# 24V_to_5V_Buck_Converter.net
KiCad netlist of a schematic drawn in Altium Designer
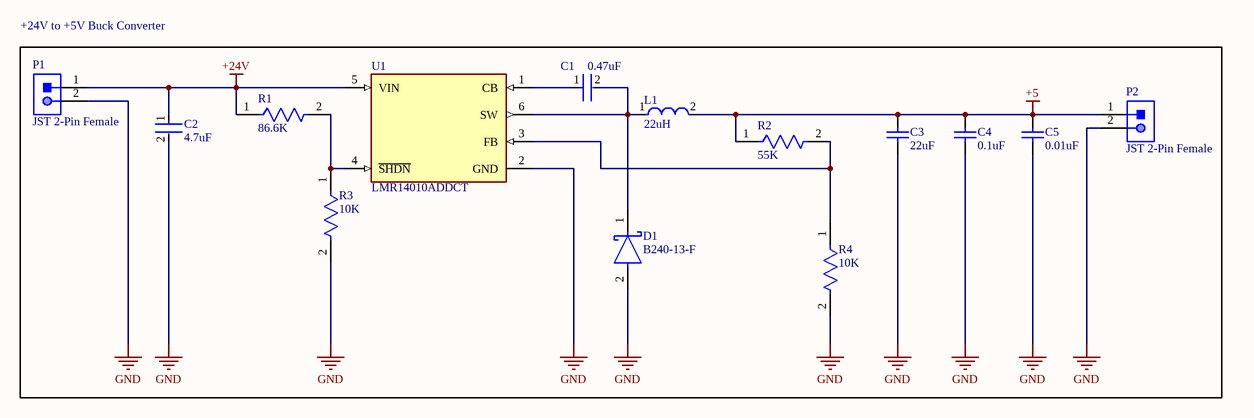
[diagram p0: 24V_to_5V_Buck_Converter.SchDoc]

(export (version "E")
  (design (tool "Eeschema 10.0.6"))
  (components
    (comp (ref "C1")
      (value "0.47uF")
      (footprint "FP-CC0603-DA-MFG")
      (description "CAP CER 0.47UF 16V X7R 0603")
      (fields
        (field (name "MANUFACTURER PART NUMBER") "CC0603KRX7R7BB474")
        (field (name "MANUFACTURER") "YAGEO")
      )
      (libsource (lib "Altium Content Vault") (part "11868f565c42a9108669ba33697ecf6"))
    )
    (comp (ref "C2")
      (value "4.7uF")
      (footprint "FP-CC1206-1_25-MFG")
      (description "CAP CER 4.7UF 50V X7R 1206")
      (fields (field (name "MANUFACTURER PART NUMBER") "CC1206KKX7R9BB475") (field (name "TOLERANCE") "0.1"))
      (libsource (lib "Altium Content Vault") (part "11868f565c42a9108669ba33697ecf6"))
    )
    (comp (ref "C3")
      (value "22uF")
      (footprint "CAPC1206(3216)190_L")
      (description "CAP 22uF 16V -20% to +80% 1206 (3216 Metric) Thickness 1.9mm SMD")
      (fields (field (name "TOLERANCE") "-20% to +80%"))
      (libsource (lib "Altium Content Vault") (part "CAP"))
    )
    (comp (ref "C4")
      (value "0.1uF")
      (footprint "CAPC1206(3216)190_L")
      (description "CAP 22uF 16V -20% to +80% 1206 (3216 Metric) Thickness 1.9mm SMD")
      (fields (field (name "TOLERANCE") "-20% to +80%"))
      (libsource (lib "Altium Content Vault") (part "CAP"))
    )
    (comp (ref "C5")
      (value "0.01uF")
      (footprint "CAPC1206(3216)190_L")
      (description "CAP 22uF 16V -20% to +80% 1206 (3216 Metric) Thickness 1.9mm SMD")
      (fields (field (name "TOLERANCE") "-20% to +80%"))
      (libsource (lib "Altium Content Vault") (part "CAP"))
    )
    (comp (ref "D1")
      (value "B240-13-F")
      (footprint "FP-SMB-MFG")
      (description "DIODE SCHOTTKY 40V 2A SMB")
      (fields
        (field (name "MANUFACTURER") "Diodes Inc.")
        (field (name "OCTOPART") "https://octopart.com/b240-13-f-diodes+inc.-325780")
      )
      (libsource (lib "Altium Content Vault") (part "1d6ec82d83fb6aee721767c19dac4b9"))
    )
    (comp (ref "L1")
      (value "22uH")
      (footprint "FP-IHLP-2525CZ-FP_2_413x3-MFG")
      (description "Commercial Inductors, Low DCR Series 22uH 2.9A 135mΩ 20%")
      (fields (field (name "TOLERANCE") "20%"))
      (libsource (lib "Altium Content Vault") (part "725321dda6339637d4d059423bc1c3c"))
    )
    (comp (ref "P1")
      (value "JST 2-Pin Female")
      (footprint "JST-S2B-PH-K-S_V")
      (fields (field (name "TOLERANCE") "20%"))
      (libsource (lib "") (part "CN-1P-M-R2_1"))
    )
    (comp (ref "P2")
      (value "JST 2-Pin Female")
      (footprint "JST-S2B-PH-K-S_V")
      (fields (field (name "TOLERANCE") "20%"))
      (libsource (lib "Altium Content Vault") (part "CN-1P-M-R2"))
    )
    (comp (ref "R1")
      (value "86.6K")
      (footprint "FP-RC0603-MFG")
      (description "RES SMD 0 OHM JUMPER 1/10W 0603")
      (fields
        (field (name "TOLERANCE") "1%")
        (field (name "OCTOPART") "https://octopart.com/rc0603fr-070rl-yageo-1180803")
      )
      (libsource (lib "Altium Content Vault") (part "1029c3af85768c4190bb7ad29bc67b5"))
    )
    (comp (ref "R2")
      (value "55K")
      (footprint "FP-RC0603-MFG")
      (description "RES SMD 0 OHM JUMPER 1/10W 0603")
      (fields
        (field (name "TOLERANCE") "1%")
        (field (name "OCTOPART") "https://octopart.com/rc0603fr-070rl-yageo-1180803")
      )
      (libsource (lib "Altium Content Vault") (part "1029c3af85768c4190bb7ad29bc67b5"))
    )
    (comp (ref "R3")
      (value "10K")
      (footprint "FP-RC0603-MFG")
      (description "RES SMD 0 OHM JUMPER 1/10W 0603")
      (fields
        (field (name "TOLERANCE") "1%")
        (field (name "OCTOPART") "https://octopart.com/rc0603fr-070rl-yageo-1180803")
      )
      (libsource (lib "Altium Content Vault") (part "1029c3af85768c4190bb7ad29bc67b5"))
    )
    (comp (ref "R4")
      (value "10K")
      (footprint "FP-RC0603-MFG")
      (description "RES SMD 0 OHM JUMPER 1/10W 0603")
      (fields
        (field (name "TOLERANCE") "1%")
        (field (name "OCTOPART") "https://octopart.com/rc0603fr-070rl-yageo-1180803")
      )
      (libsource (lib "Altium Content Vault") (part "1029c3af85768c4190bb7ad29bc67b5"))
    )
    (comp (ref "U1")
      (value "LMR14010ADDCT")
      (footprint "FP-DDC0006A-IPC_C")
      (description "IC REG BUCK ADJ 1A TSOT23-6")
      (libsource (lib "Altium Content Vault") (part "121dc64c8900d5d4b1f77199f935d68"))
    )
  )
  (nets
    (net (code "1") (name "+5") (class "Default")
      (node (ref "C3") (pin "2") (pinfunction "2_2") (pintype "passive"))
      (node (ref "C4") (pin "2") (pinfunction "2_2") (pintype "passive"))
      (node (ref "C5") (pin "2") (pinfunction "2_2") (pintype "passive"))
      (node (ref "L1") (pin "2") (pinfunction "2_2") (pintype "passive"))
      (node (ref "P2") (pin "1") (pinfunction "1_1") (pintype "passive"))
      (node (ref "R2") (pin "1") (pinfunction "1_1") (pintype "passive"))
    )
    (net (code "2") (name "+24V") (class "Default")
      (node (ref "C2") (pin "1") (pinfunction "1_1") (pintype "passive"))
      (node (ref "P1") (pin "1") (pinfunction "1_1") (pintype "passive"))
      (node (ref "R1") (pin "1") (pinfunction "1_1") (pintype "passive"))
      (node (ref "U1") (pin "5") (pinfunction "VIN_5") (pintype "input"))
    )
    (net (code "3") (name "GND") (class "Default")
      (node (ref "C2") (pin "2") (pinfunction "2_2") (pintype "passive"))
      (node (ref "C3") (pin "1") (pinfunction "1_1") (pintype "passive"))
      (node (ref "C4") (pin "1") (pinfunction "1_1") (pintype "passive"))
      (node (ref "C5") (pin "1") (pinfunction "1_1") (pintype "passive"))
      (node (ref "D1") (pin "2") (pinfunction "A_2") (pintype "passive"))
      (node (ref "P1") (pin "2") (pinfunction "2_2") (pintype "passive"))
      (node (ref "P2") (pin "2") (pinfunction "2_2") (pintype "passive"))
      (node (ref "R3") (pin "2") (pinfunction "2_2") (pintype "passive"))
      (node (ref "R4") (pin "2") (pinfunction "2_2") (pintype "passive"))
      (node (ref "U1") (pin "2") (pinfunction "GND_2") (pintype "power_in"))
    )
    (net (code "4") (name "Net-(D1-C)") (class "Default")
      (node (ref "C1") (pin "2") (pinfunction "2_2") (pintype "passive"))
      (node (ref "D1") (pin "1") (pinfunction "C_1") (pintype "passive"))
      (node (ref "L1") (pin "1") (pinfunction "1_1") (pintype "passive"))
      (node (ref "U1") (pin "6") (pinfunction "SW_6") (pintype "output"))
    )
    (net (code "5") (name "Net-(U1-CB)") (class "Default")
      (node (ref "C1") (pin "1") (pinfunction "1_1") (pintype "passive"))
      (node (ref "U1") (pin "1") (pinfunction "CB_1") (pintype "input"))
    )
    (net (code "6") (name "Net-(U1-FB)") (class "Default")
      (node (ref "R2") (pin "2") (pinfunction "2_2") (pintype "passive"))
      (node (ref "R4") (pin "1") (pinfunction "1_1") (pintype "passive"))
      (node (ref "U1") (pin "3") (pinfunction "FB_3") (pintype "input"))
    )
    (net (code "7") (name "Net-(U1-~{SHDN})") (class "Default")
      (node (ref "R1") (pin "2") (pinfunction "2_2") (pintype "passive"))
      (node (ref "R3") (pin "1") (pinfunction "1_1") (pintype "passive"))
      (node (ref "U1") (pin "4") (pinfunction "~{SHDN}_4") (pintype "input"))
    )
  )
)
